# Power.net
KiCad netlist of a schematic drawn in EAGLE
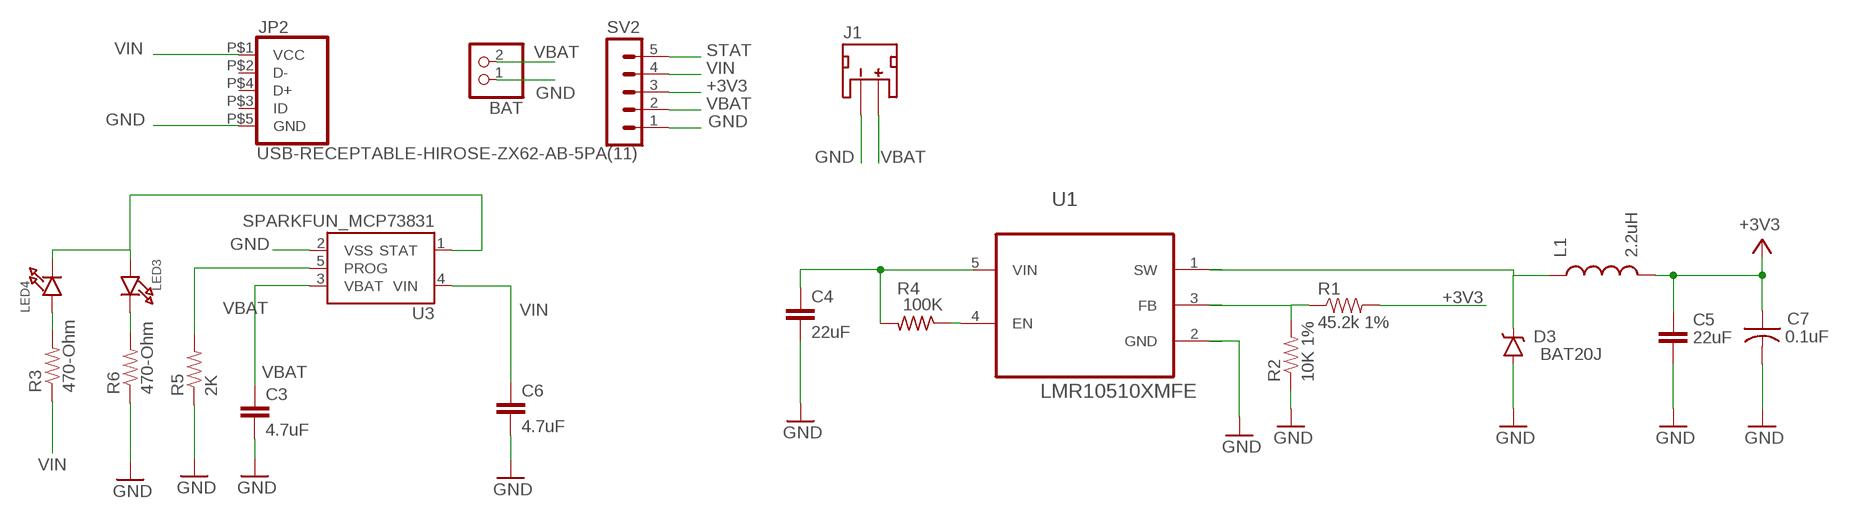
[diagram p0: schematic, sheet 1]

(export (version "E")
  (design (tool "Eeschema 10.0.6"))
  (components
    (comp (ref "BAT")
      (value "PINHD-1X2")
      (footprint "eagle-import:1X02")
      (libsource (lib "eagle-import") (part "PINHD-1X2"))
    )
    (comp (ref "C3")
      (value "4.7uF")
      (footprint "eagle-import:0603-CAP")
      (libsource (lib "eagle-import") (part "CAP0603-CAP"))
    )
    (comp (ref "C4")
      (value "22uF")
      (footprint "eagle-import:C0603")
      (libsource (lib "eagle-import") (part "C-EUC0603"))
    )
    (comp (ref "C5")
      (value "22uF")
      (footprint "eagle-import:C0603")
      (libsource (lib "eagle-import") (part "C-EUC0603"))
    )
    (comp (ref "C6")
      (value "4.7uF")
      (footprint "eagle-import:0603-CAP")
      (libsource (lib "eagle-import") (part "CAP0603-CAP"))
    )
    (comp (ref "C7")
      (value "0.1uF")
      (footprint "eagle-import:C0402")
      (libsource (lib "eagle-import") (part "C-USC0402"))
    )
    (comp (ref "D3")
      (value "BAT20J")
      (footprint "eagle-import:SOD-323")
      (libsource (lib "eagle-import") (part "DIODE-SCHOTTKY-BAT20J"))
    )
    (comp (ref "J1")
      (value "JST_2MM_MALE")
      (footprint "eagle-import:JST-2-SMD")
      (libsource (lib "eagle-import") (part "JST_2MM_MALE"))
    )
    (comp (ref "JP2")
      (value "USB-RECEPTABLE-HIROSE-ZX62-AB-5PA(11)")
      (footprint "eagle-import:HIROSE-ZX62-AB-5PA(11)")
      (libsource (lib "eagle-import") (part "USB-RECEPTABLE-HIROSE-ZX62-AB-5PA(11)"))
    )
    (comp (ref "L1")
      (value "2.2uH")
      (footprint "eagle-import:0805")
      (libsource (lib "eagle-import") (part "INDUCTOR-SPARKFUN0805"))
    )
    (comp (ref "LED3")
      (value "LED0603")
      (footprint "eagle-import:CHIPLED_0603")
      (libsource (lib "eagle-import") (part "LED0603"))
    )
    (comp (ref "LED4")
      (value "LED0603")
      (footprint "eagle-import:CHIPLED_0603")
      (libsource (lib "eagle-import") (part "LED0603"))
    )
    (comp (ref "R1")
      (value "45.2k 1%")
      (footprint "eagle-import:0603-RES")
      (libsource (lib "eagle-import") (part "RESISTOR0603"))
    )
    (comp (ref "R2")
      (value "10K 1%")
      (footprint "eagle-import:0603-RES")
      (libsource (lib "eagle-import") (part "RESISTOR0603"))
    )
    (comp (ref "R3")
      (value "470-Ohm")
      (footprint "eagle-import:0603-RES")
      (libsource (lib "eagle-import") (part "RESISTOR0603"))
    )
    (comp (ref "R4")
      (value "100K")
      (footprint "eagle-import:R0402")
      (libsource (lib "eagle-import") (part "R-US_R0402"))
    )
    (comp (ref "R5")
      (value "2K")
      (footprint "eagle-import:0603-RES")
      (libsource (lib "eagle-import") (part "RESISTOR0603"))
    )
    (comp (ref "R6")
      (value "470-Ohm")
      (footprint "eagle-import:0603-RES")
      (libsource (lib "eagle-import") (part "RESISTOR0603"))
    )
    (comp (ref "SV2")
      (value "MA05-1")
      (footprint "eagle-import:MA05-1")
      (libsource (lib "eagle-import") (part "MA05-1"))
    )
    (comp (ref "U1")
      (value "LMR10510XMFE")
      (footprint "eagle-import:SOT95P270X145-5N")
      (libsource (lib "eagle-import") (part "LMR10510XMFE"))
    )
    (comp (ref "U3")
      (value "SPARKFUN_MCP73831")
      (footprint "eagle-import:SPARKFUN_SOT23-5")
      (libsource (lib "eagle-import") (part "SPARKFUN_MCP73831"))
    )
  )
  (nets
    (net (code "1") (name "+3V3") (class "Default")
      (node (ref "C5") (pin "1") (pinfunction "1_1") (pintype "passive"))
      (node (ref "C7") (pin "1") (pinfunction "1_1") (pintype "passive"))
      (node (ref "L1") (pin "2") (pinfunction "2_2") (pintype "passive"))
      (node (ref "R1") (pin "2") (pinfunction "2_2") (pintype "passive"))
      (node (ref "SV2") (pin "3") (pinfunction "3_3") (pintype "passive"))
    )
    (net (code "2") (name "/STAT") (class "Default")
      (node (ref "LED3") (pin "A") (pinfunction "A_A") (pintype "passive"))
      (node (ref "LED4") (pin "C") (pinfunction "C_C") (pintype "passive"))
      (node (ref "SV2") (pin "5") (pinfunction "5_5") (pintype "passive"))
      (node (ref "U3") (pin "1") (pinfunction "STAT_1") (pintype "output"))
    )
    (net (code "3") (name "/VBAT") (class "Default")
      (node (ref "BAT") (pin "2") (pinfunction "2_2") (pintype "passive"))
      (node (ref "C3") (pin "1") (pinfunction "1_1") (pintype "passive"))
      (node (ref "C4") (pin "1") (pinfunction "1_1") (pintype "passive"))
      (node (ref "J1") (pin "2") (pinfunction "+_2") (pintype "bidirectional"))
      (node (ref "R4") (pin "2") (pinfunction "2_2") (pintype "passive"))
      (node (ref "SV2") (pin "2") (pinfunction "2_2") (pintype "passive"))
      (node (ref "U1") (pin "5") (pinfunction "VIN_5") (pintype "output"))
      (node (ref "U3") (pin "3") (pinfunction "VBAT_3") (pintype "power_in"))
    )
    (net (code "4") (name "/VIN") (class "Default")
      (node (ref "C6") (pin "1") (pinfunction "1_1") (pintype "passive"))
      (node (ref "JP2") (pin "P$1") (pinfunction "VCC_P$1") (pintype "bidirectional"))
      (node (ref "R3") (pin "1") (pinfunction "1_1") (pintype "passive"))
      (node (ref "SV2") (pin "4") (pinfunction "4_4") (pintype "passive"))
      (node (ref "U3") (pin "4") (pinfunction "VIN_4") (pintype "power_in"))
    )
    (net (code "5") (name "GND") (class "Default")
      (node (ref "BAT") (pin "1") (pinfunction "1_1") (pintype "passive"))
      (node (ref "C3") (pin "2") (pinfunction "2_2") (pintype "passive"))
      (node (ref "C4") (pin "2") (pinfunction "2_2") (pintype "passive"))
      (node (ref "C5") (pin "2") (pinfunction "2_2") (pintype "passive"))
      (node (ref "C6") (pin "2") (pinfunction "2_2") (pintype "passive"))
      (node (ref "C7") (pin "2") (pinfunction "2_2") (pintype "passive"))
      (node (ref "D3") (pin "A") (pinfunction "A_A") (pintype "passive"))
      (node (ref "J1") (pin "1") (pinfunction "-_1") (pintype "bidirectional"))
      (node (ref "JP2") (pin "P$5") (pinfunction "GND_P$5") (pintype "bidirectional"))
      (node (ref "R2") (pin "1") (pinfunction "1_1") (pintype "passive"))
      (node (ref "R5") (pin "1") (pinfunction "1_1") (pintype "passive"))
      (node (ref "R6") (pin "1") (pinfunction "1_1") (pintype "passive"))
      (node (ref "SV2") (pin "1") (pinfunction "1_1") (pintype "passive"))
      (node (ref "U1") (pin "2") (pinfunction "GND_2") (pintype "passive"))
      (node (ref "U3") (pin "2") (pinfunction "VSS_2") (pintype "power_in"))
    )
    (net (code "6") (name "Net-(LED3-PadC)") (class "Default")
      (node (ref "LED3") (pin "C") (pinfunction "C_C") (pintype "passive"))
      (node (ref "R6") (pin "2") (pinfunction "2_2") (pintype "passive"))
    )
    (net (code "7") (name "Net-(LED4-PadA)") (class "Default")
      (node (ref "LED4") (pin "A") (pinfunction "A_A") (pintype "passive"))
      (node (ref "R3") (pin "2") (pinfunction "2_2") (pintype "passive"))
    )
    (net (code "8") (name "Net-(U1-EN)") (class "Default")
      (node (ref "R4") (pin "1") (pinfunction "1_1") (pintype "passive"))
      (node (ref "U1") (pin "4") (pinfunction "EN_4") (pintype "output"))
    )
    (net (code "9") (name "Net-(U1-FB)") (class "Default")
      (node (ref "R1") (pin "1") (pinfunction "1_1") (pintype "passive"))
      (node (ref "R2") (pin "2") (pinfunction "2_2") (pintype "passive"))
      (node (ref "U1") (pin "3") (pinfunction "FB_3") (pintype "input"))
    )
    (net (code "10") (name "Net-(U1-SW)") (class "Default")
      (node (ref "D3") (pin "C") (pinfunction "C_C") (pintype "passive"))
      (node (ref "L1") (pin "1") (pinfunction "1_1") (pintype "passive"))
      (node (ref "U1") (pin "1") (pinfunction "SW_1") (pintype "input"))
    )
    (net (code "11") (name "Net-(U3-PROG)") (class "Default")
      (node (ref "R5") (pin "2") (pinfunction "2_2") (pintype "passive"))
      (node (ref "U3") (pin "5") (pinfunction "PROG_5") (pintype "input"))
    )
    (net (code "12") (name "unconnected-(J1-PAD1-PadNC1)") (class "Default")
      (node (ref "J1") (pin "NC1") (pinfunction "PAD1_NC1") (pintype "bidirectional"))
    )
    (net (code "13") (name "unconnected-(J1-PAD2-PadNC2)") (class "Default")
      (node (ref "J1") (pin "NC2") (pinfunction "PAD2_NC2") (pintype "bidirectional"))
    )
    (net (code "14") (name "unconnected-(JP2-D+-PadP$4)") (class "Default")
      (node (ref "JP2") (pin "P$4") (pinfunction "D+_P$4") (pintype "bidirectional"))
    )
    (net (code "15") (name "unconnected-(JP2-D--PadP$2)") (class "Default")
      (node (ref "JP2") (pin "P$2") (pinfunction "D-_P$2") (pintype "bidirectional"))
    )
    (net (code "16") (name "unconnected-(JP2-ID-PadP$3)") (class "Default")
      (node (ref "JP2") (pin "P$3") (pinfunction "ID_P$3") (pintype "bidirectional"))
    )
  )
)
